# P20_Mini_PCIe_4G_5G.net
KiCad netlist of a schematic drawn in Altium Designer
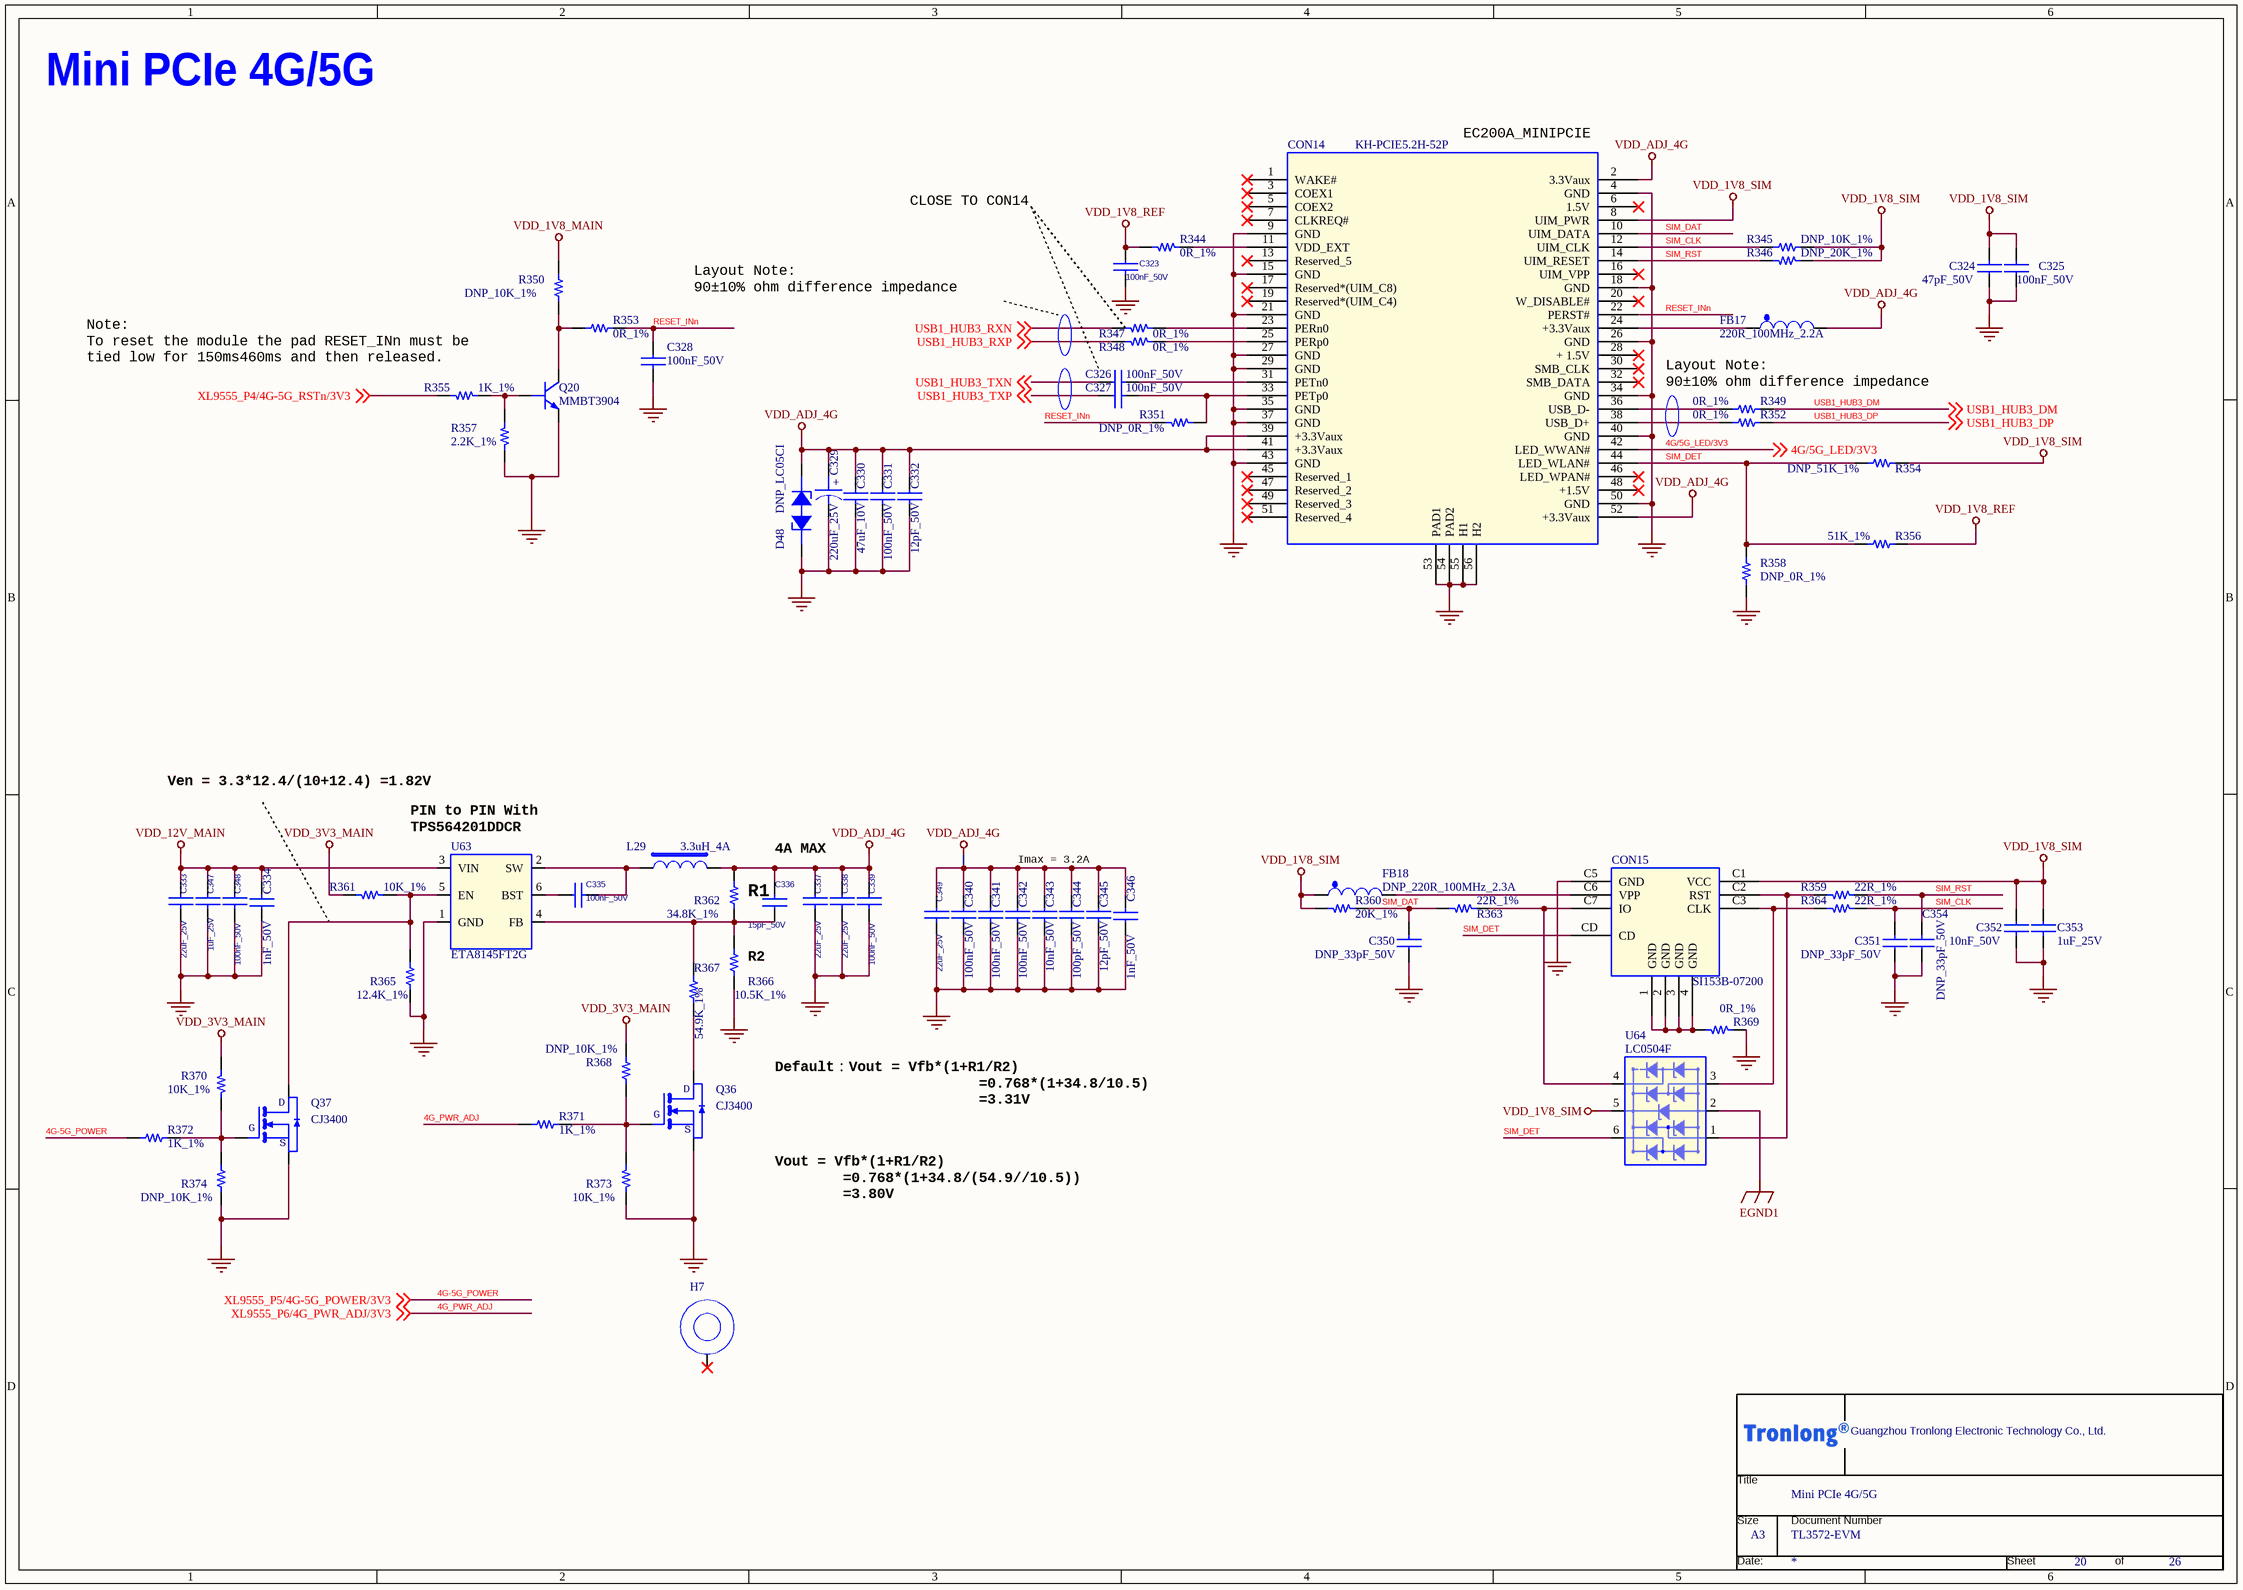
[diagram p0: P20_Mini PCIe 4G_5G.SchDoc]

(export (version "E")
  (design (tool "Eeschema 10.0.6"))
  (components
    (comp (ref "*")
      (value "Tronlong_TITTLE_20211115")
      (fields
        (field (name "DOC") "TL3572-EVM")
        (field (name "TITLE") "Mini PCIe 4G/5G")
        (field (name "ORGNAME") "Guangzhou Tronlong Electronic Technology Co., Ltd.")
        (field (name "PAGE SIZE") "A3")
        (field (name "PAGE NUMBER") "20")
        (field (name "PAGE COUNT") "26")
      )
      (libsource (lib "*") (part "Tronlong_TITTLE_20211115"))
    )
    (comp (ref "C323")
      (value "100nF_50V")
      (footprint "C0402")
      (description "贴片陶瓷电容,100nF,10%,50V,X7R")
      (fields
        (field (name "MANUFACTURER") "广东风华高新科技股份有限公司（FH）")
        (field (name "MANUFACTURER PARTNUMBER") "0402B104K500NT")
      )
      (libsource (lib "*") (part "CAP NP_Dup2"))
    )
    (comp (ref "C324")
      (value "47pF_50V")
      (footprint "C0402")
      (description "CC0402JRNPO9BN470")
      (fields
        (field (name "MANUFACTURER") "广州创龙")
        (field (name "MANUFACTURER PARTNUMBER") "47pF,5%,C0402,50V,（X7R,X5R,COG,NPO或X7S）")
      )
      (libsource (lib "*") (part "CAP NP"))
    )
    (comp (ref "C325")
      (value "100nF_50V")
      (footprint "C0402")
      (description "贴片陶瓷电容,100nF,10%,50V,X7R")
      (fields
        (field (name "MANUFACTURER") "广东风华高新科技股份有限公司（FH）")
        (field (name "MANUFACTURER PARTNUMBER") "0402B104K500NT")
      )
      (libsource (lib "*") (part "CAP NP"))
    )
    (comp (ref "C326")
      (value "100nF_50V")
      (footprint "C0402")
      (description "贴片陶瓷电容,100nF,10%,50V,X7R")
      (fields
        (field (name "MANUFACTURER") "广东风华高新科技股份有限公司（FH）")
        (field (name "MANUFACTURER PARTNUMBER") "0402B104K500NT")
      )
      (libsource (lib "*") (part "CAP NP_Dup2"))
    )
    (comp (ref "C327")
      (value "100nF_50V")
      (footprint "C0402")
      (description "贴片陶瓷电容,100nF,10%,50V,X7R")
      (fields
        (field (name "MANUFACTURER") "广东风华高新科技股份有限公司（FH）")
        (field (name "MANUFACTURER PARTNUMBER") "0402B104K500NT")
      )
      (libsource (lib "*") (part "CAP NP_Dup2"))
    )
    (comp (ref "C328")
      (value "100nF_50V")
      (footprint "C0402")
      (description "贴片陶瓷电容,100nF,10%,50V,X7R")
      (fields
        (field (name "MANUFACTURER PARTNUMBER") "0402B104K500NT")
        (field (name "MANUFACTURER") "广东风华高新科技股份有限公司（FH）")
      )
      (libsource (lib "*") (part "CAP NP"))
    )
    (comp (ref "C329")
      (value "220uF_25V")
      (footprint "SMD-ALU-L66H66")
      (description "贴片式铝电解电容,220uF,20%,25V")
      (fields
        (field (name "MANUFACTURER PARTNUMBER") "HDS1E221M0607VG")
        (field (name "MANUFACTURER") "东莞市合粤电子有限公司（Heyue）")
      )
      (libsource (lib "*") (part "CAP POL"))
    )
    (comp (ref "C330")
      (value "47uF_10V")
      (footprint "C0805")
      (description "贴片陶瓷电容,47uF,20%,10V,X5R")
      (fields
        (field (name "MANUFACTURER PARTNUMBER") "0805X476M100NT")
        (field (name "MANUFACTURER") "广东风华高新科技股份有限公司（FH）")
      )
      (libsource (lib "*") (part "CAP NP"))
    )
    (comp (ref "C331")
      (value "100nF_50V")
      (footprint "C0402")
      (description "贴片陶瓷电容,100nF,10%,50V,X7R")
      (fields
        (field (name "MANUFACTURER PARTNUMBER") "0402B104K500NT")
        (field (name "MANUFACTURER") "广东风华高新科技股份有限公司（FH）")
      )
      (libsource (lib "*") (part "CAP NP"))
    )
    (comp (ref "C332")
      (value "12pF_50V")
      (footprint "C0402")
      (description "贴片陶瓷电容,12pF,5%,50V,COG")
      (fields
        (field (name "MANUFACTURER PARTNUMBER") "0402CG120J500NT")
        (field (name "MANUFACTURER") "广东风华高新科技股份有限公司（FH）")
      )
      (libsource (lib "*") (part "CAP NP"))
    )
    (comp (ref "C333")
      (value "22uF_25V")
      (footprint "C0805")
      (description "贴片陶瓷电容,22uF,20%,25V,X5R")
      (fields
        (field (name "MANUFACTURER PARTNUMBER") "0805X226M250NT")
        (field (name "MANUFACTURER") "广东风华高新科技股份有限公司（FH）")
      )
      (libsource (lib "*") (part "CAP NP_Dup2"))
    )
    (comp (ref "C334")
      (value "1nF_50V")
      (footprint "C0402")
      (description "贴片陶瓷电容,1nF,10%,50V,X7R")
      (fields
        (field (name "TOLERANCE") "±10%")
        (field (name "MANUFACTURER") "广东风华高新科技股份有限公司（FH）")
        (field (name "CREATED BY") "JJJ")
      )
      (libsource (lib "*") (part "CAP NP_1"))
    )
    (comp (ref "C335")
      (value "100nF_50V")
      (footprint "C0402")
      (description "贴片陶瓷电容,100nF,10%,50V,X7R")
      (fields
        (field (name "MANUFACTURER") "广东风华高新科技股份有限公司（FH）")
        (field (name "MANUFACTURER PARTNUMBER") "0402B104K500NT")
      )
      (libsource (lib "*") (part "CAP NP_Dup2"))
    )
    (comp (ref "C336")
      (value "15pF_50V")
      (footprint "C0603")
      (description "CL10C150JB8NNNC,CC0603JRNPO9BN150")
      (fields
        (field (name "MANUFACTURER") "广州创龙")
        (field (name "MANUFACTURER PARTNUMBER") "15pF,5%,C0603,50V,（X7R,X5R,COG,NPO或X7S）")
      )
      (libsource (lib "*") (part "CAP NP_Dup2"))
    )
    (comp (ref "C337")
      (value "22uF_25V")
      (footprint "C0805")
      (description "贴片陶瓷电容,22uF,20%,25V,X5R")
      (fields
        (field (name "MANUFACTURER PARTNUMBER") "0805X226M250NT")
        (field (name "MANUFACTURER") "广东风华高新科技股份有限公司（FH）")
      )
      (libsource (lib "*") (part "CAP NP_Dup2"))
    )
    (comp (ref "C338")
      (value "22uF_25V")
      (footprint "C0805")
      (description "贴片陶瓷电容,22uF,20%,25V,X5R")
      (fields
        (field (name "MANUFACTURER") "广东风华高新科技股份有限公司（FH）")
        (field (name "MANUFACTURER PARTNUMBER") "0805X226M250NT")
      )
      (libsource (lib "*") (part "CAP NP_Dup2"))
    )
    (comp (ref "C339")
      (value "100nF_50V")
      (footprint "C0402")
      (description "贴片陶瓷电容,100nF,10%,50V,X7R")
      (fields
        (field (name "MANUFACTURER PARTNUMBER") "0402B104K500NT")
        (field (name "MANUFACTURER") "广东风华高新科技股份有限公司（FH）")
      )
      (libsource (lib "*") (part "CAP NP_Dup2"))
    )
    (comp (ref "C340")
      (value "100nF_50V")
      (footprint "C0402")
      (description "贴片陶瓷电容,100nF,10%,50V,X7R")
      (fields
        (field (name "MANUFACTURER") "广东风华高新科技股份有限公司（FH）")
        (field (name "MANUFACTURER PARTNUMBER") "0402B104K500NT")
      )
      (libsource (lib "*") (part "CAP NP"))
    )
    (comp (ref "C341")
      (value "100nF_50V")
      (footprint "C0402")
      (description "贴片陶瓷电容,100nF,10%,50V,X7R")
      (fields
        (field (name "MANUFACTURER") "广东风华高新科技股份有限公司（FH）")
        (field (name "MANUFACTURER PARTNUMBER") "0402B104K500NT")
      )
      (libsource (lib "*") (part "CAP NP"))
    )
    (comp (ref "C342")
      (value "100nF_50V")
      (footprint "C0402")
      (description "贴片陶瓷电容,100nF,10%,50V,X7R")
      (fields
        (field (name "MANUFACTURER PARTNUMBER") "0402B104K500NT")
        (field (name "MANUFACTURER") "广东风华高新科技股份有限公司（FH）")
      )
      (libsource (lib "*") (part "CAP NP"))
    )
    (comp (ref "C343")
      (value "10nF_50V")
      (footprint "C0402")
      (description "贴片陶瓷电容,10nF,10%,50V,X7R")
      (fields
        (field (name "MANUFACTURER PARTNUMBER") "0402B103K500NT")
        (field (name "MANUFACTURER") "广东风华高新科技股份有限公司（FH）")
      )
      (libsource (lib "*") (part "CAP NP"))
    )
    (comp (ref "C344")
      (value "100pF_50V")
      (footprint "C0402")
      (description "贴片陶瓷电容,100pF,5%,50V,COG")
      (fields
        (field (name "MANUFACTURER") "广东风华高新科技股份有限公司（FH）")
        (field (name "MANUFACTURER PARTNUMBER") "0402CG101J500NT")
      )
      (libsource (lib "*") (part "CAP NP"))
    )
    (comp (ref "C345")
      (value "12pF_50V")
      (footprint "C0402")
      (description "贴片陶瓷电容,12pF,5%,50V,COG")
      (fields
        (field (name "MANUFACTURER") "广东风华高新科技股份有限公司（FH）")
        (field (name "MANUFACTURER PARTNUMBER") "0402CG120J500NT")
      )
      (libsource (lib "*") (part "CAP NP"))
    )
    (comp (ref "C346")
      (value "1nF_50V")
      (footprint "C0402")
      (description "贴片陶瓷电容,1nF,10%,50V,X7R")
      (fields
        (field (name "MANUFACTURER PARTNUMBER") "0402B102K500NT")
        (field (name "MANUFACTURER") "广东风华高新科技股份有限公司（FH）")
        (field (name "CREATED BY") "JJJ")
      )
      (libsource (lib "*") (part "CAP NP_1"))
    )
    (comp (ref "C347")
      (value "1uF_25V")
      (footprint "C0402")
      (description "贴片陶瓷电容,1uF,10%,25V,X5R")
      (fields
        (field (name "MANUFACTURER PARTNUMBER") "0402X105K250NT")
        (field (name "MANUFACTURER") "广东风华高新科技股份有限公司（FH）")
      )
      (libsource (lib "*") (part "CAP NP_Dup2"))
    )
    (comp (ref "C348")
      (value "100nF_50V")
      (footprint "C0402")
      (description "贴片陶瓷电容,100nF,10%,50V,X7R")
      (fields
        (field (name "MANUFACTURER") "广东风华高新科技股份有限公司（FH）")
        (field (name "MANUFACTURER PARTNUMBER") "0402B104K500NT")
      )
      (libsource (lib "*") (part "CAP NP_Dup2"))
    )
    (comp (ref "C349")
      (value "22uF_25V")
      (footprint "C0805")
      (description "贴片陶瓷电容,22uF,20%,25V,X5R")
      (fields
        (field (name "MANUFACTURER") "广东风华高新科技股份有限公司（FH）")
        (field (name "MANUFACTURER PARTNUMBER") "0805X226M250NT")
      )
      (libsource (lib "*") (part "CAP NP_Dup2"))
    )
    (comp (ref "C350")
      (value "DNP_33pF_50V")
      (footprint "C0402")
      (description "贴片陶瓷电容,33pF,5%,50V,COG")
      (fields
        (field (name "MANUFACTURER PARTNUMBER") "0402CG330J500NT")
        (field (name "MANUFACTURER") "广东风华高新科技股份有限公司（FH）")
      )
      (libsource (lib "*") (part "CAP NP_Dup2"))
    )
    (comp (ref "C351")
      (value "DNP_33pF_50V")
      (footprint "C0402")
      (description "贴片陶瓷电容,33pF,5%,50V,COG")
      (fields
        (field (name "MANUFACTURER") "广东风华高新科技股份有限公司（FH）")
        (field (name "MANUFACTURER PARTNUMBER") "0402CG330J500NT")
      )
      (libsource (lib "*") (part "CAP NP_Dup2"))
    )
    (comp (ref "C352")
      (value "10nF_50V")
      (footprint "C0402")
      (description "贴片陶瓷电容,10nF,10%,50V,X7R")
      (fields
        (field (name "MANUFACTURER PARTNUMBER") "0402B103K500NT")
        (field (name "MANUFACTURER") "广东风华高新科技股份有限公司（FH）")
      )
      (libsource (lib "*") (part "CAP NP_Dup2"))
    )
    (comp (ref "C353")
      (value "1uF_25V")
      (footprint "C0402")
      (description "贴片陶瓷电容,1uF,10%,25V,X5R")
      (fields
        (field (name "MANUFACTURER PARTNUMBER") "0402X105K250NT")
        (field (name "MANUFACTURER") "广东风华高新科技股份有限公司（FH）")
      )
      (libsource (lib "*") (part "CAP NP_Dup2"))
    )
    (comp (ref "C354")
      (value "DNP_33pF_50V")
      (footprint "C0402")
      (description "贴片陶瓷电容,33pF,5%,50V,COG")
      (fields
        (field (name "MANUFACTURER PARTNUMBER") "0402CG330J500NT")
        (field (name "MANUFACTURER") "广东风华高新科技股份有限公司（FH）")
      )
      (libsource (lib "*") (part "CAP NP_Dup2"))
    )
    (comp (ref "CON14")
      (value "KH-PCIE5.2H-52P")
      (footprint "aaa-pci-047-k01")
      (description "贴片mini PCIE插槽,52P,0.8mm间距,母座,H=5.2mm")
      (fields (field (name "MANUFACTURER") "深圳市金航标电子有限公司(kinghelm)"))
      (libsource (lib "*") (part "CON_mSATA_2"))
    )
    (comp (ref "CON15")
      (value "SI153B-07200")
      (footprint "SIM_SI124C-01200")
      (description "Nano SIM卡座,7P,1.27mm间距,自弹,带检测脚")
      (fields (field (name "MANUFACTURER") "深圳市爱特姆科技有限公司（ATOM）"))
      (libsource (lib "*") (part "SI124C-01200_3"))
    )
    (comp (ref "D48")
      (value "DNP_LC05CI")
      (footprint "SOD323_BI")
      (description "TVS二极管,VRWM=5V,VBR=6V,一组,双向,30KV,30KV")
      (fields
        (field (name "MANUFACTURER PART NUMBER") "PESD3V3L1BA")
        (field (name "MANUFACTURER PARTNUMBER") "LC05CI")
      )
      (libsource (lib "*") (part "DIODE BREAKDOWN_2"))
    )
    (comp (ref "FB17")
      (value "220R_100MHz_2.2A")
      (footprint "L0603")
      (description "磁珠,50mΩ,2.2A,220R@100MHz")
      (fields
        (field (name "MANUFACTURER") "深圳顺络电子股份有限公司（Sunlord）")
        (field (name "MANUFACTURER PARTNUMBER") "UPZ1608U221-2R2TF")
      )
      (libsource (lib "*") (part "FERRITE BEAD_Dup1"))
    )
    (comp (ref "FB18")
      (value "DNP_220R_100MHz_2.3A")
      (footprint "L0603")
      (description "磁珠,50mΩ,2.3A,220R@100MHz")
      (fields
        (field (name "MANUFACTURER PARTNUMBER") "UPZ1608U221-2R3TF")
        (field (name "MANUFACTURER") "深圳顺络电子股份有限公司（Sunlord）")
      )
      (libsource (lib "*") (part "FB_0"))
    )
    (comp (ref "H7") (value "HOLE") (footprint "NHOLE_C5_BT") (libsource (lib "*") (part "HOLE")))
    (comp (ref "L29")
      (value "3.3uH_4A")
      (footprint "SMD-L5452M-2P")
      (description "贴片功率电感,3.3uH,0.058Ω,Isat=5A,Irms=4A")
      (fields
        (field (name "MANUFACTURER PARTNUMBER") "CSAB0518-3R3M")
        (field (name "MANUFACTURER") "深圳市科达嘉电子有限公司（CODACA）")
      )
      (libsource (lib "*") (part "INDUCTOR"))
    )
    (comp (ref "Q20")
      (value "MMBT3904")
      (footprint "SOT23-3_DBZ3")
      (description "BJT,NPN,Vceo=40V,Ic=200mA,fT=300MHz,PD=200mW")
      (fields (field (name "MANUFACTURER") "江苏长晶科技股份有限公司（JSCJ）"))
      (libsource (lib "*") (part "MMBT3904/SOT"))
    )
    (comp (ref "Q36")
      (value "CJ3400")
      (footprint "SOT23-3")
      (description "MOSFET,N沟道,VDSS=30V,VGSS=±12V,ID=5.8A,PD=0.35W,VGS(th)=1.4V")
      (fields (field (name "MANUFACTURER") "江苏长晶科技股份有限公司（JSCJ）"))
      (libsource (lib "*") (part "MOSFET N SOT"))
    )
    (comp (ref "Q37")
      (value "CJ3400")
      (footprint "SOT23-3")
      (description "MOSFET,N沟道,VDSS=30V,VGSS=±12V,ID=5.8A,PD=0.35W,VGS(th)=1.4V")
      (fields (field (name "MANUFACTURER") "江苏长晶科技股份有限公司（JSCJ）"))
      (libsource (lib "*") (part "MOSFET N SOT"))
    )
    (comp (ref "R344")
      (value "0R_1%")
      (footprint "R0402")
      (description "贴片电阻,0R,±1%,1/16W")
      (fields
        (field (name "MANUFACTURER") "广东风华高新科技股份有限公司（FH）")
        (field (name "MANUFACTURER PARTNUMBER") "RC-02000FT")
      )
      (libsource (lib "*") (part "Resistor_Dup3"))
    )
    (comp (ref "R345")
      (value "DNP_10K_1%")
      (footprint "R0402")
      (description "贴片电阻,10K,±1%,1/16W")
      (fields
        (field (name "MANUFACTURER") "广东风华高新科技股份有限公司（FH）")
        (field (name "MANUFACTURER PARTNUMBER") "RC-02K1002FT")
      )
      (libsource (lib "*") (part "Resistor_Dup3"))
    )
    (comp (ref "R346")
      (value "DNP_20K_1%")
      (footprint "R0402")
      (description "贴片电阻,20K,±1%,1/16W")
      (fields
        (field (name "MANUFACTURER PARTNUMBER") "RC-02K2002FT")
        (field (name "MANUFACTURER") "广东风华高新科技股份有限公司（FH）")
      )
      (libsource (lib "*") (part "R 1%"))
    )
    (comp (ref "R347")
      (value "0R_1%")
      (footprint "R0402")
      (description "贴片电阻,0R,±1%,1/16W")
      (fields
        (field (name "MANUFACTURER PARTNUMBER") "RC-02000FT")
        (field (name "MANUFACTURER") "广东风华高新科技股份有限公司（FH）")
      )
      (libsource (lib "*") (part "Resistor_Dup3"))
    )
    (comp (ref "R348")
      (value "0R_1%")
      (footprint "R0402")
      (description "贴片电阻,0R,±1%,1/16W")
      (fields
        (field (name "MANUFACTURER") "广东风华高新科技股份有限公司（FH）")
        (field (name "MANUFACTURER PARTNUMBER") "RC-02000FT")
      )
      (libsource (lib "*") (part "Resistor_Dup3"))
    )
    (comp (ref "R349")
      (value "0R_1%")
      (footprint "R0402")
      (description "贴片电阻,0R,±1%,1/16W")
      (fields
        (field (name "MANUFACTURER PARTNUMBER") "RC-02000FT")
        (field (name "MANUFACTURER") "广东风华高新科技股份有限公司（FH）")
      )
      (libsource (lib "*") (part "R 1%"))
    )
    (comp (ref "R350")
      (value "DNP_10K_1%")
      (footprint "R0402")
      (description "贴片电阻,10K,±1%,1/16W")
      (fields (field (name "MANUFACTURER") "广东风华高新科技股份有限公司（FH）") (field (name "TOLERANCE") "5%"))
      (libsource (lib "*") (part "Resistor_Dup1"))
    )
    (comp (ref "R351")
      (value "DNP_0R_1%")
      (footprint "R0402")
      (description "贴片电阻,0R,±1%,1/16W")
      (fields
        (field (name "MANUFACTURER") "广东风华高新科技股份有限公司（FH）")
        (field (name "MANUFACTURER PARTNUMBER") "RC-02000FT")
      )
      (libsource (lib "*") (part "Resistor_Dup3"))
    )
    (comp (ref "R352")
      (value "0R_1%")
      (footprint "R0402")
      (description "贴片电阻,0R,±1%,1/16W")
      (fields
        (field (name "MANUFACTURER") "广东风华高新科技股份有限公司（FH）")
        (field (name "MANUFACTURER PARTNUMBER") "RC-02000FT")
      )
      (libsource (lib "*") (part "R 1%"))
    )
    (comp (ref "R353")
      (value "0R_1%")
      (footprint "R0402")
      (description "贴片电阻,0R,±1%,1/16W")
      (fields
        (field (name "MANUFACTURER PARTNUMBER") "RC-02000FT")
        (field (name "MANUFACTURER") "广东风华高新科技股份有限公司（FH）")
      )
      (libsource (lib "*") (part "R 1%"))
    )
    (comp (ref "R354")
      (value "DNP_51K_1%")
      (footprint "R0402")
      (description "RC0402FR-0751KL,0402WGF5102TCE")
      (fields
        (field (name "MANUFACTURER PARTNUMBER") "51K,±1%,R0402,≥1/16W")
        (field (name "MANUFACTURER") "广州创龙")
      )
      (libsource (lib "*") (part "R 1%"))
    )
    (comp (ref "R355")
      (value "1K_1%")
      (footprint "R0402")
      (description "贴片电阻,1K,±1%,1/16W")
      (fields
        (field (name "MANUFACTURER") "广东风华高新科技股份有限公司（FH）")
        (field (name "MANUFACTURER PARTNUMBER") "RC-02K1001FT")
      )
      (libsource (lib "*") (part "Resistor_Dup4"))
    )
    (comp (ref "R356")
      (value "51K_1%")
      (footprint "R0402")
      (description "RC0402FR-0751KL,0402WGF5102TCE")
      (fields
        (field (name "MANUFACTURER PARTNUMBER") "51K,±1%,R0402,≥1/16W")
        (field (name "MANUFACTURER") "广州创龙")
      )
      (libsource (lib "*") (part "R 1%"))
    )
    (comp (ref "R357")
      (value "2.2K_1%")
      (footprint "R0402")
      (description "贴片电阻,2.2K,±1%,1/16W")
      (fields
        (field (name "MANUFACTURER") "广东风华高新科技股份有限公司（FH）")
        (field (name "MANUFACTURER PARTNUMBER") "RC-02K2201FT")
      )
      (libsource (lib "*") (part "Resistor_Dup4"))
    )
    (comp (ref "R358")
      (value "DNP_0R_1%")
      (footprint "R0402")
      (description "贴片电阻,0R,±1%,1/16W")
      (fields
        (field (name "MANUFACTURER PARTNUMBER") "RC-02000FT")
        (field (name "MANUFACTURER") "广东风华高新科技股份有限公司（FH）")
      )
      (libsource (lib "*") (part "R 1%"))
    )
    (comp (ref "R359")
      (value "22R_1%")
      (footprint "R0402")
      (description "贴片电阻,22R,±1%,1/16W")
      (fields
        (field (name "MANUFACTURER PARTNUMBER") "RC-02K22R0FT")
        (field (name "MANUFACTURER") "广东风华高新科技股份有限公司（FH）")
      )
      (libsource (lib "*") (part "Resistor_Dup3"))
    )
    (comp (ref "R360")
      (value "20K_1%")
      (footprint "R0603")
      (description "贴片电阻,20K,±1%,1/10W")
      (fields
        (field (name "MANUFACTURER PARTNUMBER") "RS-03K2002FT")
        (field (name "MANUFACTURER") "广东风华高新科技股份有限公司（FH）")
      )
      (libsource (lib "*") (part "R 1%"))
    )
    (comp (ref "R361")
      (value "10K_1%")
      (footprint "R0402")
      (description "贴片电阻,10K,±1%,1/16W")
      (fields
        (field (name "MANUFACTURER PARTNUMBER") "RC-02K1002FT")
        (field (name "MANUFACTURER") "广东风华高新科技股份有限公司（FH）")
      )
      (libsource (lib "*") (part "Resistor_Dup4"))
    )
    (comp (ref "R362")
      (value "34.8K_1%")
      (footprint "R0402")
      (description "0402WGF3482TCE")
      (fields
        (field (name "MANUFACTURER") "广州创龙")
        (field (name "MANUFACTURER PARTNUMBER") "34.8K,±1%,R0402,≥1/16W")
      )
      (libsource (lib "*") (part "Resistor_Dup3"))
    )
    (comp (ref "R363")
      (value "22R_1%")
      (footprint "R0402")
      (description "贴片电阻,22R,±1%,1/16W")
      (fields
        (field (name "MANUFACTURER") "广东风华高新科技股份有限公司（FH）")
        (field (name "MANUFACTURER PARTNUMBER") "RC-02K22R0FT")
      )
      (libsource (lib "*") (part "Resistor_Dup3"))
    )
    (comp (ref "R364")
      (value "22R_1%")
      (footprint "R0402")
      (description "贴片电阻,22R,±1%,1/16W")
      (fields
        (field (name "MANUFACTURER PARTNUMBER") "RC-02K22R0FT")
        (field (name "MANUFACTURER") "广东风华高新科技股份有限公司（FH）")
      )
      (libsource (lib "*") (part "Resistor_Dup3"))
    )
    (comp (ref "R365")
      (value "12.4K_1%")
      (footprint "R0402")
      (description "0402WGF1242TCE")
      (fields
        (field (name "MANUFACTURER PARTNUMBER") "12.4K,±1%,R0402,≥1/16W")
        (field (name "MANUFACTURER") "广州创龙")
      )
      (libsource (lib "*") (part "Resistor_Dup3"))
    )
    (comp (ref "R366")
      (value "10.5K_1%")
      (footprint "R0402")
      (description "RC0402FR-0710K5L,0402WGF1052TCE")
      (fields
        (field (name "MANUFACTURER") "广州创龙")
        (field (name "MANUFACTURER PARTNUMBER") "10.5K,±1%,R0402,≥1/16W")
      )
      (libsource (lib "*") (part "Resistor_Dup3"))
    )
    (comp (ref "R367")
      (value "54.9K_1%")
      (footprint "R0402")
      (description "RC0402FR-0754K9L,0402WGF5492TCE")
      (fields
        (field (name "MANUFACTURER") "广州创龙")
        (field (name "MANUFACTURER PARTNUMBER") "54.9K,±1%,R0402,≥1/16W")
      )
      (libsource (lib "*") (part "Resistor_Dup3"))
    )
    (comp (ref "R368")
      (value "DNP_10K_1%")
      (footprint "R0402")
      (description "贴片电阻,10K,±1%,1/16W")
      (fields
        (field (name "MANUFACTURER") "广东风华高新科技股份有限公司（FH）")
        (field (name "MANUFACTURER PARTNUMBER") "RC-02K1002FT")
      )
      (libsource (lib "*") (part "Resistor_Dup3"))
    )
    (comp (ref "R369")
      (value "0R_1%")
      (footprint "R0402")
      (description "贴片电阻,0R,±1%,1/16W")
      (fields
        (field (name "MANUFACTURER PARTNUMBER") "RC-02000FT")
        (field (name "MANUFACTURER") "广东风华高新科技股份有限公司（FH）")
      )
      (libsource (lib "*") (part "Resistor_Dup3"))
    )
    (comp (ref "R370")
      (value "10K_1%")
      (footprint "R0402")
      (description "贴片电阻,10K,±1%,1/16W")
      (fields
        (field (name "MANUFACTURER") "广东风华高新科技股份有限公司（FH）")
        (field (name "MANUFACTURER PARTNUMBER") "RC-02K1002FT")
      )
      (libsource (lib "*") (part "Resistor_Dup4"))
    )
    (comp (ref "R371")
      (value "1K_1%")
      (footprint "R0402")
      (description "贴片电阻,1K,±1%,1/16W")
      (fields
        (field (name "MANUFACTURER") "广东风华高新科技股份有限公司（FH）")
        (field (name "MISTRAL PART NO") "110009031036-R")
      )
      (libsource (lib "*") (part "Resistor_Dup3"))
    )
    (comp (ref "R372")
      (value "1K_1%")
      (footprint "R0402")
      (description "贴片电阻,1K,±1%,1/16W")
      (fields
        (field (name "MANUFACTURER PARTNUMBER") "RC-02K1001FT")
        (field (name "DISTRIBUTOR_PART_NUMBER") "NA")
      )
      (libsource (lib "*") (part "Resistor_Dup3"))
    )
    (comp (ref "R373")
      (value "10K_1%")
      (footprint "R0402")
      (description "贴片电阻,10K,±1%,1/16W")
      (fields
        (field (name "MANUFACTURER") "广东风华高新科技股份有限公司（FH）")
        (field (name "MANUFACTURER PARTNUMBER") "RC-02K1002FT")
      )
      (libsource (lib "*") (part "Resistor_Dup4"))
    )
    (comp (ref "R374")
      (value "DNP_10K_1%")
      (footprint "R0402")
      (description "贴片电阻,10K,±1%,1/16W")
      (fields
        (field (name "MANUFACTURER") "广东风华高新科技股份有限公司（FH）")
        (field (name "MANUFACTURER PARTNUMBER") "RC-02K1002FT")
      )
      (libsource (lib "*") (part "Resistor_Dup3"))
    )
    (comp (ref "U63")
      (value "ETA8145FT2G")
      (footprint "SOT-23-6L")
      (description "DC/DC,Buck,Vin:4.5V~17V,Vout:0.8-5.5V,4A,1路")
      (fields (field (name "MANUFACTURER") "钰泰半导体股份有限公司（ETA）"))
      (libsource (lib "*") (part "WD1304E30_2"))
    )
    (comp (ref "U64")
      (value "LC0504F")
      (footprint "SOT363")
      (description "ESD二极管,VRWM=5V,VBR=6V,四组,单向,8KV,15KV")
      (fields
        (field (name "MANUFACTURER PART NUMBER") "PRTR5V0U4Y")
        (field (name "MANUFACTURER") "上海雷卯电子科技有限公司（Leiditech）")
      )
      (libsource (lib "*") (part "PRTR5V0U4Y_0"))
    )
  )
  (nets
    (net (code "1") (name "/RESET_INn") (class "Default")
      (node (ref "C328") (pin "1") (pinfunction "1_1") (pintype "passive"))
      (node (ref "CON14") (pin "22") (pinfunction "PERST#_22") (pintype "passive"))
      (node (ref "R351") (pin "1") (pinfunction "1_1") (pintype "passive"))
      (node (ref "R353") (pin "2") (pinfunction "2_2") (pintype "passive"))
    )
    (net (code "2") (name "/SIM_CLK") (class "Default")
      (node (ref "C351") (pin "2") (pinfunction "2_2") (pintype "passive"))
      (node (ref "CON14") (pin "12") (pinfunction "UIM_CLK_12") (pintype "passive"))
      (node (ref "R345") (pin "1") (pinfunction "1_1") (pintype "passive"))
      (node (ref "R364") (pin "2") (pinfunction "2_2") (pintype "passive"))
    )
    (net (code "3") (name "/SIM_DAT") (class "Default")
      (node (ref "C350") (pin "2") (pinfunction "2_2") (pintype "passive"))
      (node (ref "CON14") (pin "10") (pinfunction "UIM_DATA_10") (pintype "passive"))
      (node (ref "R360") (pin "2") (pinfunction "2_2") (pintype "passive"))
      (node (ref "R363") (pin "1") (pinfunction "1_1") (pintype "passive"))
    )
    (net (code "4") (name "/SIM_DET") (class "Default")
      (node (ref "CON14") (pin "44") (pinfunction "LED_WLAN#_44") (pintype "passive"))
      (node (ref "CON15") (pin "CD") (pinfunction "CD_CD") (pintype "passive"))
      (node (ref "R354") (pin "2") (pinfunction "2_2") (pintype "passive"))
      (node (ref "R356") (pin "2") (pinfunction "2_2") (pintype "passive"))
      (node (ref "R358") (pin "1") (pinfunction "1_1") (pintype "passive"))
      (node (ref "U64") (pin "6") (pinfunction "6_6") (pintype "passive"))
    )
    (net (code "5") (name "/SIM_RST") (class "Default")
      (node (ref "C354") (pin "2") (pinfunction "2_2") (pintype "passive"))
      (node (ref "CON14") (pin "14") (pinfunction "UIM_RESET_14") (pintype "passive"))
      (node (ref "R346") (pin "1") (pinfunction "1_1") (pintype "passive"))
      (node (ref "R359") (pin "2") (pinfunction "2_2") (pintype "passive"))
    )
    (net (code "6") (name "4G{slash}5G_LED{slash}3V3") (class "Default")
      (node (ref "CON14") (pin "42") (pinfunction "LED_WWAN#_42") (pintype "passive"))
    )
    (net (code "7") (name "EGND1") (class "Default")
      (node (ref "U64") (pin "2") (pinfunction "2_2") (pintype "passive"))
    )
    (net (code "8") (name "GND") (class "Default")
      (node (ref "C323") (pin "2") (pinfunction "2_2") (pintype "passive"))
      (node (ref "C324") (pin "1") (pinfunction "1_1") (pintype "passive"))
      (node (ref "C325") (pin "1") (pinfunction "1_1") (pintype "passive"))
      (node (ref "C328") (pin "2") (pinfunction "2_2") (pintype "passive"))
      (node (ref "C329") (pin "2") (pinfunction "2_2") (pintype "passive"))
      (node (ref "C330") (pin "2") (pinfunction "2_2") (pintype "passive"))
      (node (ref "C331") (pin "2") (pinfunction "2_2") (pintype "passive"))
      (node (ref "C332") (pin "2") (pinfunction "2_2") (pintype "passive"))
      (node (ref "C333") (pin "2") (pinfunction "2_2") (pintype "passive"))
      (node (ref "C334") (pin "1") (pinfunction "1_1") (pintype "passive"))
      (node (ref "C337") (pin "2") (pinfunction "2_2") (pintype "passive"))
      (node (ref "C338") (pin "2") (pinfunction "2_2") (pintype "passive"))
      (node (ref "C339") (pin "2") (pinfunction "2_2") (pintype "passive"))
      (node (ref "C340") (pin "2") (pinfunction "2_2") (pintype "passive"))
      (node (ref "C341") (pin "2") (pinfunction "2_2") (pintype "passive"))
      (node (ref "C342") (pin "2") (pinfunction "2_2") (pintype "passive"))
      (node (ref "C343") (pin "2") (pinfunction "2_2") (pintype "passive"))
      (node (ref "C344") (pin "2") (pinfunction "2_2") (pintype "passive"))
      (node (ref "C345") (pin "2") (pinfunction "2_2") (pintype "passive"))
      (node (ref "C346") (pin "1") (pinfunction "1_1") (pintype "passive"))
      (node (ref "C347") (pin "2") (pinfunction "2_2") (pintype "passive"))
      (node (ref "C348") (pin "2") (pinfunction "2_2") (pintype "passive"))
      (node (ref "C349") (pin "2") (pinfunction "2_2") (pintype "passive"))
      (node (ref "C350") (pin "1") (pinfunction "1_1") (pintype "passive"))
      (node (ref "C351") (pin "1") (pinfunction "1_1") (pintype "passive"))
      (node (ref "C352") (pin "2") (pinfunction "2_2") (pintype "passive"))
      (node (ref "C353") (pin "2") (pinfunction "2_2") (pintype "passive"))
      (node (ref "C354") (pin "1") (pinfunction "1_1") (pintype "passive"))
      (node (ref "CON14") (pin "15") (pinfunction "GND_15") (pintype "power_in"))
      (node (ref "CON14") (pin "18") (pinfunction "GND_18") (pintype "power_in"))
      (node (ref "CON14") (pin "21") (pinfunction "GND_21") (pintype "power_in"))
      (node (ref "CON14") (pin "26") (pinfunction "GND_26") (pintype "power_in"))
      (node (ref "CON14") (pin "27") (pinfunction "GND_27") (pintype "power_in"))
      (node (ref "CON14") (pin "29") (pinfunction "GND_29") (pintype "power_in"))
      (node (ref "CON14") (pin "34") (pinfunction "GND_34") (pintype "power_in"))
      (node (ref "CON14") (pin "35") (pinfunction "GND_35") (pintype "power_in"))
      (node (ref "CON14") (pin "37") (pinfunction "GND_37") (pintype "power_in"))
      (node (ref "CON14") (pin "4") (pinfunction "GND_4") (pintype "power_in"))
      (node (ref "CON14") (pin "40") (pinfunction "GND_40") (pintype "power_in"))
      (node (ref "CON14") (pin "43") (pinfunction "GND_43") (pintype "power_in"))
      (node (ref "CON14") (pin "50") (pinfunction "GND_50") (pintype "power_in"))
      (node (ref "CON14") (pin "53") (pinfunction "PAD1_53") (pintype "passive"))
      (node (ref "CON14") (pin "54") (pinfunction "PAD2_54") (pintype "passive"))
      (node (ref "CON14") (pin "55") (pinfunction "H1_55") (pintype "passive"))
      (node (ref "CON14") (pin "56") (pinfunction "H2_56") (pintype "passive"))
      (node (ref "CON14") (pin "9") (pinfunction "GND_9") (pintype "power_in"))
      (node (ref "CON15") (pin "C5") (pinfunction "GND_C5") (pintype "power_in"))
      (node (ref "D48") (pin "2") (pinfunction "CATHODE2_2") (pintype "passive"))
      (node (ref "Q20") (pin "2") (pinfunction "E_2") (pintype "passive"))
      (node (ref "Q36") (pin "2") (pinfunction "E_2") (pintype "passive"))
      (node (ref "Q37") (pin "2") (pinfunction "E_2") (pintype "passive"))
      (node (ref "R357") (pin "2") (pinfunction "2_2") (pintype "passive"))
      (node (ref "R358") (pin "2") (pinfunction "2_2") (pintype "passive"))
      (node (ref "R365") (pin "1") (pinfunction "1_1") (pintype "passive"))
      (node (ref "R366") (pin "1") (pinfunction "1_1") (pintype "passive"))
      (node (ref "R369") (pin "1") (pinfunction "1_1") (pintype "passive"))
      (node (ref "R373") (pin "2") (pinfunction "2_2") (pintype "passive"))
      (node (ref "R374") (pin "2") (pinfunction "2_2") (pintype "passive"))
      (node (ref "U63") (pin "1") (pinfunction "GND_1") (pintype "power_in"))
    )
    (net (code "9") (name "Net-(CON14-+3.3Vaux-Pad24)") (class "Default")
      (node (ref "CON14") (pin "24") (pinfunction "+3.3Vaux_24") (pintype "power_in"))
      (node (ref "FB17") (pin "1") (pinfunction "1_1") (pintype "passive"))
    )
    (net (code "10") (name "Net-(CON14-PERn0)") (class "Default")
      (node (ref "CON14") (pin "23") (pinfunction "PERn0_23") (pintype "passive"))
      (node (ref "R347") (pin "2") (pinfunction "2_2") (pintype "passive"))
    )
    (net (code "11") (name "Net-(CON14-PERp0)") (class "Default")
      (node (ref "CON14") (pin "25") (pinfunction "PERp0_25") (pintype "passive"))
      (node (ref "R348") (pin "2") (pinfunction "2_2") (pintype "passive"))
    )
    (net (code "12") (name "Net-(CON14-PETn0)") (class "Default")
      (node (ref "C326") (pin "2") (pinfunction "2_2") (pintype "passive"))
      (node (ref "CON14") (pin "31") (pinfunction "PETn0_31") (pintype "passive"))
    )
    (net (code "13") (name "Net-(CON14-PETp0)") (class "Default")
      (node (ref "C327") (pin "2") (pinfunction "2_2") (pintype "passive"))
      (node (ref "CON14") (pin "33") (pinfunction "PETp0_33") (pintype "passive"))
      (node (ref "R351") (pin "2") (pinfunction "2_2") (pintype "passive"))
    )
    (net (code "14") (name "Net-(CON14-USB_D+)") (class "Default")
      (node (ref "CON14") (pin "38") (pinfunction "USB_D+_38") (pintype "passive"))
      (node (ref "R352") (pin "1") (pinfunction "1_1") (pintype "passive"))
    )
    (net (code "15") (name "Net-(CON14-USB_D-)") (class "Default")
      (node (ref "CON14") (pin "36") (pinfunction "USB_D-_36") (pintype "passive"))
      (node (ref "R349") (pin "1") (pinfunction "1_1") (pintype "passive"))
    )
    (net (code "16") (name "Net-(CON14-VDD_EXT)") (class "Default")
      (node (ref "CON14") (pin "11") (pinfunction "VDD_EXT_11") (pintype "passive"))
      (node (ref "R344") (pin "2") (pinfunction "2_2") (pintype "passive"))
    )
    (net (code "17") (name "Net-(CON15-CLK)") (class "Default")
      (node (ref "CON15") (pin "C3") (pinfunction "CLK_C3") (pintype "passive"))
      (node (ref "R364") (pin "1") (pinfunction "1_1") (pintype "passive"))
      (node (ref "U64") (pin "3") (pinfunction "3_3") (pintype "passive"))
    )
    (net (code "18") (name "Net-(CON15-GND-Pad1)") (class "Default")
      (node (ref "CON15") (pin "1") (pinfunction "GND_1") (pintype "power_in"))
      (node (ref "CON15") (pin "2") (pinfunction "GND_2") (pintype "power_in"))
      (node (ref "CON15") (pin "3") (pinfunction "GND_3") (pintype "power_in"))
      (node (ref "CON15") (pin "4") (pinfunction "GND_4") (pintype "power_in"))
      (node (ref "R369") (pin "2") (pinfunction "2_2") (pintype "passive"))
    )
    (net (code "19") (name "Net-(CON15-IO)") (class "Default")
      (node (ref "CON15") (pin "C7") (pinfunction "IO_C7") (pintype "passive"))
      (node (ref "R363") (pin "2") (pinfunction "2_2") (pintype "passive"))
      (node (ref "U64") (pin "4") (pinfunction "4_4") (pintype "passive"))
    )
    (net (code "20") (name "Net-(CON15-RST)") (class "Default")
      (node (ref "CON15") (pin "C2") (pinfunction "RST_C2") (pintype "passive"))
      (node (ref "R359") (pin "1") (pinfunction "1_1") (pintype "passive"))
      (node (ref "U64") (pin "1") (pinfunction "1_1") (pintype "passive"))
    )
    (net (code "21") (name "Net-(CON15-VPP)") (class "Default")
      (node (ref "CON15") (pin "C6") (pinfunction "VPP_C6") (pintype "power_in"))
      (node (ref "FB18") (pin "2") (pinfunction "2_2") (pintype "passive"))
    )
    (net (code "22") (name "Net-(Q20-B)") (class "Default")
      (node (ref "Q20") (pin "1") (pinfunction "B_1") (pintype "passive"))
      (node (ref "R355") (pin "2") (pinfunction "2_2") (pintype "passive"))
      (node (ref "R357") (pin "1") (pinfunction "1_1") (pintype "passive"))
    )
    (net (code "23") (name "Net-(Q20-C)") (class "Default")
      (node (ref "Q20") (pin "3") (pinfunction "C_3") (pintype "passive"))
      (node (ref "R350") (pin "1") (pinfunction "1_1") (pintype "passive"))
      (node (ref "R353") (pin "1") (pinfunction "1_1") (pintype "passive"))
    )
    (net (code "24") (name "Net-(Q36-B)") (class "Default")
      (node (ref "Q36") (pin "1") (pinfunction "B_1") (pintype "passive"))
      (node (ref "R368") (pin "2") (pinfunction "2_2") (pintype "passive"))
      (node (ref "R371") (pin "2") (pinfunction "2_2") (pintype "passive"))
      (node (ref "R373") (pin "1") (pinfunction "1_1") (pintype "passive"))
    )
    (net (code "25") (name "Net-(Q36-C)") (class "Default")
      (node (ref "Q36") (pin "3") (pinfunction "C_3") (pintype "passive"))
      (node (ref "R367") (pin "1") (pinfunction "1_1") (pintype "passive"))
    )
    (net (code "26") (name "Net-(Q37-B)") (class "Default")
      (node (ref "Q37") (pin "1") (pinfunction "B_1") (pintype "passive"))
      (node (ref "R370") (pin "1") (pinfunction "1_1") (pintype "passive"))
      (node (ref "R372") (pin "2") (pinfunction "2_2") (pintype "passive"))
      (node (ref "R374") (pin "1") (pinfunction "1_1") (pintype "passive"))
    )
    (net (code "27") (name "Net-(Q37-C)") (class "Default")
      (node (ref "Q37") (pin "3") (pinfunction "C_3") (pintype "passive"))
      (node (ref "R361") (pin "2") (pinfunction "2_2") (pintype "passive"))
      (node (ref "R365") (pin "2") (pinfunction "2_2") (pintype "passive"))
      (node (ref "U63") (pin "5") (pinfunction "EN_5") (pintype "passive"))
    )
    (net (code "28") (name "Net-(U63-BST)") (class "Default")
      (node (ref "C335") (pin "1") (pinfunction "1_1") (pintype "passive"))
      (node (ref "U63") (pin "6") (pinfunction "BST_6") (pintype "passive"))
    )
    (net (code "29") (name "Net-(U63-FB)") (class "Default")
      (node (ref "C336") (pin "1") (pinfunction "1_1") (pintype "passive"))
      (node (ref "R362") (pin "1") (pinfunction "1_1") (pintype "passive"))
      (node (ref "R366") (pin "2") (pinfunction "2_2") (pintype "passive"))
      (node (ref "R367") (pin "2") (pinfunction "2_2") (pintype "passive"))
      (node (ref "U63") (pin "4") (pinfunction "FB_4") (pintype "passive"))
    )
    (net (code "30") (name "Net-(U63-SW)") (class "Default")
      (node (ref "C335") (pin "2") (pinfunction "2_2") (pintype "passive"))
      (node (ref "L29") (pin "1") (pinfunction "1_1") (pintype "passive"))
      (node (ref "U63") (pin "2") (pinfunction "SW_2") (pintype "passive"))
    )
    (net (code "31") (name "USB1_HUB3_DM") (class "Default")
      (node (ref "R349") (pin "2") (pinfunction "2_2") (pintype "passive"))
    )
    (net (code "32") (name "USB1_HUB3_DP") (class "Default")
      (node (ref "R352") (pin "2") (pinfunction "2_2") (pintype "passive"))
    )
    (net (code "33") (name "USB1_HUB3_RXN") (class "Default")
      (node (ref "R347") (pin "1") (pinfunction "1_1") (pintype "passive"))
    )
    (net (code "34") (name "USB1_HUB3_RXP") (class "Default")
      (node (ref "R348") (pin "1") (pinfunction "1_1") (pintype "passive"))
    )
    (net (code "35") (name "USB1_HUB3_TXN") (class "Default")
      (node (ref "C326") (pin "1") (pinfunction "1_1") (pintype "passive"))
    )
    (net (code "36") (name "USB1_HUB3_TXP") (class "Default")
      (node (ref "C327") (pin "1") (pinfunction "1_1") (pintype "passive"))
    )
    (net (code "37") (name "VDD_1V8_MAIN") (class "Default")
      (node (ref "R350") (pin "2") (pinfunction "2_2") (pintype "passive"))
    )
    (net (code "38") (name "VDD_1V8_REF") (class "Default")
      (node (ref "C323") (pin "1") (pinfunction "1_1") (pintype "passive"))
      (node (ref "R344") (pin "1") (pinfunction "1_1") (pintype "passive"))
      (node (ref "R356") (pin "1") (pinfunction "1_1") (pintype "passive"))
    )
    (net (code "39") (name "VDD_1V8_SIM") (class "Default")
      (node (ref "C324") (pin "2") (pinfunction "2_2") (pintype "passive"))
      (node (ref "C325") (pin "2") (pinfunction "2_2") (pintype "passive"))
      (node (ref "C352") (pin "1") (pinfunction "1_1") (pintype "passive"))
      (node (ref "C353") (pin "1") (pinfunction "1_1") (pintype "passive"))
      (node (ref "CON14") (pin "8") (pinfunction "UIM_PWR_8") (pintype "passive"))
      (node (ref "CON15") (pin "C1") (pinfunction "VCC_C1") (pintype "power_in"))
      (node (ref "FB18") (pin "1") (pinfunction "1_1") (pintype "passive"))
      (node (ref "R345") (pin "2") (pinfunction "2_2") (pintype "passive"))
      (node (ref "R346") (pin "2") (pinfunction "2_2") (pintype "passive"))
      (node (ref "R354") (pin "1") (pinfunction "1_1") (pintype "passive"))
      (node (ref "R360") (pin "1") (pinfunction "1_1") (pintype "passive"))
      (node (ref "U64") (pin "5") (pinfunction "5_5") (pintype "passive"))
    )
    (net (code "40") (name "VDD_3V3_MAIN") (class "Default")
      (node (ref "R361") (pin "1") (pinfunction "1_1") (pintype "passive"))
      (node (ref "R368") (pin "1") (pinfunction "1_1") (pintype "passive"))
      (node (ref "R370") (pin "2") (pinfunction "2_2") (pintype "passive"))
    )
    (net (code "41") (name "VDD_12V_MAIN") (class "Default")
      (node (ref "C333") (pin "1") (pinfunction "1_1") (pintype "passive"))
      (node (ref "C334") (pin "2") (pinfunction "2_2") (pintype "passive"))
      (node (ref "C347") (pin "1") (pinfunction "1_1") (pintype "passive"))
      (node (ref "C348") (pin "1") (pinfunction "1_1") (pintype "passive"))
      (node (ref "U63") (pin "3") (pinfunction "VIN_3") (pintype "power_in"))
    )
    (net (code "42") (name "VDD_ADJ_4G") (class "Default")
      (node (ref "C329") (pin "1") (pinfunction "1_1") (pintype "passive"))
      (node (ref "C330") (pin "1") (pinfunction "1_1") (pintype "passive"))
      (node (ref "C331") (pin "1") (pinfunction "1_1") (pintype "passive"))
      (node (ref "C332") (pin "1") (pinfunction "1_1") (pintype "passive"))
      (node (ref "C336") (pin "2") (pinfunction "2_2") (pintype "passive"))
      (node (ref "C337") (pin "1") (pinfunction "1_1") (pintype "passive"))
      (node (ref "C338") (pin "1") (pinfunction "1_1") (pintype "passive"))
      (node (ref "C339") (pin "1") (pinfunction "1_1") (pintype "passive"))
      (node (ref "C340") (pin "1") (pinfunction "1_1") (pintype "passive"))
      (node (ref "C341") (pin "1") (pinfunction "1_1") (pintype "passive"))
      (node (ref "C342") (pin "1") (pinfunction "1_1") (pintype "passive"))
      (node (ref "C343") (pin "1") (pinfunction "1_1") (pintype "passive"))
      (node (ref "C344") (pin "1") (pinfunction "1_1") (pintype "passive"))
      (node (ref "C345") (pin "1") (pinfunction "1_1") (pintype "passive"))
      (node (ref "C346") (pin "2") (pinfunction "2_2") (pintype "passive"))
      (node (ref "C349") (pin "1") (pinfunction "1_1") (pintype "passive"))
      (node (ref "CON14") (pin "2") (pinfunction "3.3Vaux_2") (pintype "power_in"))
      (node (ref "CON14") (pin "39") (pinfunction "+3.3Vaux_39") (pintype "power_in"))
      (node (ref "CON14") (pin "41") (pinfunction "+3.3Vaux_41") (pintype "power_in"))
      (node (ref "CON14") (pin "52") (pinfunction "+3.3Vaux_52") (pintype "power_in"))
      (node (ref "D48") (pin "1") (pinfunction "ANODE1_1") (pintype "passive"))
      (node (ref "FB17") (pin "2") (pinfunction "2_2") (pintype "passive"))
      (node (ref "L29") (pin "2") (pinfunction "2_2") (pintype "passive"))
      (node (ref "R362") (pin "2") (pinfunction "2_2") (pintype "passive"))
    )
    (net (code "43") (name "XL9555_P4{slash}4G-5G_RSTn{slash}3V3") (class "Default")
      (node (ref "R355") (pin "1") (pinfunction "1_1") (pintype "passive"))
    )
    (net (code "44") (name "XL9555_P5{slash}4G-5G_POWER{slash}3V3") (class "Default")
      (node (ref "R372") (pin "1") (pinfunction "1_1") (pintype "passive"))
    )
    (net (code "45") (name "XL9555_P6{slash}4G_PWR_ADJ{slash}3V3") (class "Default")
      (node (ref "R371") (pin "1") (pinfunction "1_1") (pintype "passive"))
    )
    (net (code "46") (name "unconnected-(CON14-+1.5V-Pad48)") (class "Default")
      (node (ref "CON14") (pin "48") (pinfunction "+1.5V_48") (pintype "passive+no_connect"))
    )
    (net (code "47") (name "unconnected-(CON14-+_1.5V-Pad28)") (class "Default")
      (node (ref "CON14") (pin "28") (pinfunction "+_1.5V_28") (pintype "passive+no_connect"))
    )
    (net (code "48") (name "unconnected-(CON14-1.5V-Pad6)") (class "Default")
      (node (ref "CON14") (pin "6") (pinfunction "1.5V_6") (pintype "passive+no_connect"))
    )
    (net (code "49") (name "unconnected-(CON14-CLKREQ#-Pad7)") (class "Default")
      (node (ref "CON14") (pin "7") (pinfunction "CLKREQ#_7") (pintype "passive+no_connect"))
    )
    (net (code "50") (name "unconnected-(CON14-COEX1-Pad3)") (class "Default")
      (node (ref "CON14") (pin "3") (pinfunction "COEX1_3") (pintype "passive+no_connect"))
    )
    (net (code "51") (name "unconnected-(CON14-COEX2-Pad5)") (class "Default")
      (node (ref "CON14") (pin "5") (pinfunction "COEX2_5") (pintype "passive+no_connect"))
    )
    (net (code "52") (name "unconnected-(CON14-LED_WPAN#-Pad46)") (class "Default")
      (node (ref "CON14") (pin "46") (pinfunction "LED_WPAN#_46") (pintype "passive+no_connect"))
    )
    (net (code "53") (name "unconnected-(CON14-Reserved*(UIM_C4)-Pad19)") (class "Default")
      (node (ref "CON14") (pin "19") (pinfunction "Reserved*(UIM_C4)_19") (pintype "passive+no_connect"))
    )
    (net (code "54") (name "unconnected-(CON14-Reserved*(UIM_C8)-Pad17)") (class "Default")
      (node (ref "CON14") (pin "17") (pinfunction "Reserved*(UIM_C8)_17") (pintype "passive+no_connect"))
    )
    (net (code "55") (name "unconnected-(CON14-Reserved_1-Pad45)") (class "Default")
      (node (ref "CON14") (pin "45") (pinfunction "Reserved_1_45") (pintype "passive+no_connect"))
    )
    (net (code "56") (name "unconnected-(CON14-Reserved_2-Pad47)") (class "Default")
      (node (ref "CON14") (pin "47") (pinfunction "Reserved_2_47") (pintype "passive+no_connect"))
    )
    (net (code "57") (name "unconnected-(CON14-Reserved_3-Pad49)") (class "Default")
      (node (ref "CON14") (pin "49") (pinfunction "Reserved_3_49") (pintype "passive+no_connect"))
    )
    (net (code "58") (name "unconnected-(CON14-Reserved_4-Pad51)") (class "Default")
      (node (ref "CON14") (pin "51") (pinfunction "Reserved_4_51") (pintype "passive+no_connect"))
    )
    (net (code "59") (name "unconnected-(CON14-Reserved_5-Pad13)") (class "Default")
      (node (ref "CON14") (pin "13") (pinfunction "Reserved_5_13") (pintype "passive+no_connect"))
    )
    (net (code "60") (name "unconnected-(CON14-SMB_CLK-Pad30)") (class "Default")
      (node (ref "CON14") (pin "30") (pinfunction "SMB_CLK_30") (pintype "passive+no_connect"))
    )
    (net (code "61") (name "unconnected-(CON14-SMB_DATA-Pad32)") (class "Default")
      (node (ref "CON14") (pin "32") (pinfunction "SMB_DATA_32") (pintype "passive+no_connect"))
    )
    (net (code "62") (name "unconnected-(CON14-UIM_VPP-Pad16)") (class "Default")
      (node (ref "CON14") (pin "16") (pinfunction "UIM_VPP_16") (pintype "passive+no_connect"))
    )
    (net (code "63") (name "unconnected-(CON14-WAKE#-Pad1)") (class "Default")
      (node (ref "CON14") (pin "1") (pinfunction "WAKE#_1") (pintype "passive+no_connect"))
    )
    (net (code "64") (name "unconnected-(CON14-W_DISABLE#-Pad20)") (class "Default")
      (node (ref "CON14") (pin "20") (pinfunction "W_DISABLE#_20") (pintype "passive+no_connect"))
    )
    (net (code "65") (name "unconnected-(H7-Pad1)") (class "Default")
      (node (ref "H7") (pin "1") (pinfunction "1_1") (pintype "passive+no_connect"))
    )
  )
)
